# v1_1.net
KiCad netlist of a schematic drawn in EAGLE
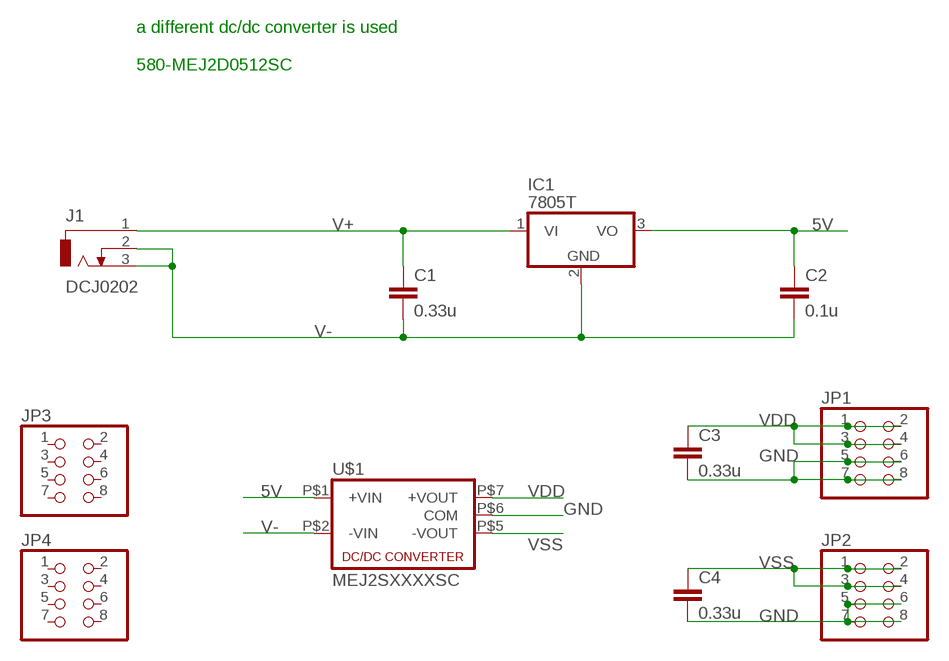
[diagram p0: schematic, sheet 1]

(export (version "E")
  (design (tool "Eeschema 10.0.6"))
  (components
    (comp (ref "C1")
      (value "0.33u")
      (footprint "eagle-import:C050-045X075")
      (libsource (lib "eagle-import") (part "C-EU050-045X075"))
    )
    (comp (ref "C2")
      (value "0.1u")
      (footprint "eagle-import:C050-045X075")
      (libsource (lib "eagle-import") (part "C-EU050-045X075"))
    )
    (comp (ref "C3")
      (value "0.33u")
      (footprint "eagle-import:C050-045X075")
      (libsource (lib "eagle-import") (part "C-EU050-045X075"))
    )
    (comp (ref "C4")
      (value "0.33u")
      (footprint "eagle-import:C050-045X075")
      (libsource (lib "eagle-import") (part "C-EU050-045X075"))
    )
    (comp (ref "IC1")
      (value "7805T")
      (footprint "eagle-import:TO220H")
      (libsource (lib "eagle-import") (part "78T05"))
    )
    (comp (ref "J1")
      (value "DCJ0202")
      (footprint "eagle-import:DCJ0202")
      (libsource (lib "eagle-import") (part "DCJ0202"))
    )
    (comp (ref "JP1")
      (value "PINHD-2X4")
      (footprint "eagle-import:2X04")
      (libsource (lib "eagle-import") (part "PINHD-2X4"))
    )
    (comp (ref "JP2")
      (value "PINHD-2X4")
      (footprint "eagle-import:2X04")
      (libsource (lib "eagle-import") (part "PINHD-2X4"))
    )
    (comp (ref "JP3")
      (value "PINHD-2X4")
      (footprint "eagle-import:2X04")
      (libsource (lib "eagle-import") (part "PINHD-2X4"))
    )
    (comp (ref "JP4")
      (value "PINHD-2X4")
      (footprint "eagle-import:2X04")
      (libsource (lib "eagle-import") (part "PINHD-2X4"))
    )
    (comp (ref "U$1")
      (value "MEJ2SXXXXSC")
      (footprint "eagle-import:NMA")
      (libsource (lib "eagle-import") (part "MEJ2SXXXXSC"))
    )
  )
  (nets
    (net (code "1") (name "/5V") (class "Default")
      (node (ref "C2") (pin "1") (pinfunction "1_1") (pintype "passive"))
      (node (ref "IC1") (pin "3") (pinfunction "VO_3") (pintype "passive"))
      (node (ref "U$1") (pin "P$1") (pinfunction "+VIN_P$1") (pintype "passive"))
    )
    (net (code "2") (name "/GND") (class "Default")
      (node (ref "C3") (pin "2") (pinfunction "2_2") (pintype "passive"))
      (node (ref "C4") (pin "2") (pinfunction "2_2") (pintype "passive"))
      (node (ref "JP1") (pin "5") (pinfunction "5_5") (pintype "passive"))
      (node (ref "JP1") (pin "6") (pinfunction "6_6") (pintype "passive"))
      (node (ref "JP1") (pin "7") (pinfunction "7_7") (pintype "passive"))
      (node (ref "JP1") (pin "8") (pinfunction "8_8") (pintype "passive"))
      (node (ref "JP2") (pin "5") (pinfunction "5_5") (pintype "passive"))
      (node (ref "JP2") (pin "6") (pinfunction "6_6") (pintype "passive"))
      (node (ref "JP2") (pin "7") (pinfunction "7_7") (pintype "passive"))
      (node (ref "JP2") (pin "8") (pinfunction "8_8") (pintype "passive"))
      (node (ref "U$1") (pin "P$6") (pinfunction "COM_P$6") (pintype "passive"))
    )
    (net (code "3") (name "/V+") (class "Default")
      (node (ref "C1") (pin "1") (pinfunction "1_1") (pintype "passive"))
      (node (ref "IC1") (pin "1") (pinfunction "VI_1") (pintype "input"))
      (node (ref "J1") (pin "1") (pinfunction "1_1") (pintype "passive"))
    )
    (net (code "4") (name "/V-") (class "Default")
      (node (ref "C1") (pin "2") (pinfunction "2_2") (pintype "passive"))
      (node (ref "C2") (pin "2") (pinfunction "2_2") (pintype "passive"))
      (node (ref "IC1") (pin "2") (pinfunction "GND_2") (pintype "passive"))
      (node (ref "J1") (pin "2") (pinfunction "2_2") (pintype "passive"))
      (node (ref "J1") (pin "3") (pinfunction "3_3") (pintype "passive"))
      (node (ref "U$1") (pin "P$2") (pinfunction "-VIN_P$2") (pintype "passive"))
    )
    (net (code "5") (name "/VDD") (class "Default")
      (node (ref "C3") (pin "1") (pinfunction "1_1") (pintype "passive"))
      (node (ref "JP1") (pin "1") (pinfunction "1_1") (pintype "passive"))
      (node (ref "JP1") (pin "2") (pinfunction "2_2") (pintype "passive"))
      (node (ref "JP1") (pin "3") (pinfunction "3_3") (pintype "passive"))
      (node (ref "JP1") (pin "4") (pinfunction "4_4") (pintype "passive"))
      (node (ref "U$1") (pin "P$7") (pinfunction "+VOUT_P$7") (pintype "passive"))
    )
    (net (code "6") (name "/VSS") (class "Default")
      (node (ref "C4") (pin "1") (pinfunction "1_1") (pintype "passive"))
      (node (ref "JP2") (pin "1") (pinfunction "1_1") (pintype "passive"))
      (node (ref "JP2") (pin "2") (pinfunction "2_2") (pintype "passive"))
      (node (ref "JP2") (pin "3") (pinfunction "3_3") (pintype "passive"))
      (node (ref "JP2") (pin "4") (pinfunction "4_4") (pintype "passive"))
      (node (ref "U$1") (pin "P$5") (pinfunction "-VOUT_P$5") (pintype "passive"))
    )
    (net (code "7") (name "unconnected-(JP3-Pad1)") (class "Default")
      (node (ref "JP3") (pin "1") (pinfunction "1_1") (pintype "passive"))
    )
    (net (code "8") (name "unconnected-(JP3-Pad2)") (class "Default")
      (node (ref "JP3") (pin "2") (pinfunction "2_2") (pintype "passive"))
    )
    (net (code "9") (name "unconnected-(JP3-Pad3)") (class "Default")
      (node (ref "JP3") (pin "3") (pinfunction "3_3") (pintype "passive"))
    )
    (net (code "10") (name "unconnected-(JP3-Pad4)") (class "Default")
      (node (ref "JP3") (pin "4") (pinfunction "4_4") (pintype "passive"))
    )
    (net (code "11") (name "unconnected-(JP3-Pad5)") (class "Default")
      (node (ref "JP3") (pin "5") (pinfunction "5_5") (pintype "passive"))
    )
    (net (code "12") (name "unconnected-(JP3-Pad6)") (class "Default")
      (node (ref "JP3") (pin "6") (pinfunction "6_6") (pintype "passive"))
    )
    (net (code "13") (name "unconnected-(JP3-Pad7)") (class "Default")
      (node (ref "JP3") (pin "7") (pinfunction "7_7") (pintype "passive"))
    )
    (net (code "14") (name "unconnected-(JP3-Pad8)") (class "Default")
      (node (ref "JP3") (pin "8") (pinfunction "8_8") (pintype "passive"))
    )
    (net (code "15") (name "unconnected-(JP4-Pad1)") (class "Default")
      (node (ref "JP4") (pin "1") (pinfunction "1_1") (pintype "passive"))
    )
    (net (code "16") (name "unconnected-(JP4-Pad2)") (class "Default")
      (node (ref "JP4") (pin "2") (pinfunction "2_2") (pintype "passive"))
    )
    (net (code "17") (name "unconnected-(JP4-Pad3)") (class "Default")
      (node (ref "JP4") (pin "3") (pinfunction "3_3") (pintype "passive"))
    )
    (net (code "18") (name "unconnected-(JP4-Pad4)") (class "Default")
      (node (ref "JP4") (pin "4") (pinfunction "4_4") (pintype "passive"))
    )
    (net (code "19") (name "unconnected-(JP4-Pad5)") (class "Default")
      (node (ref "JP4") (pin "5") (pinfunction "5_5") (pintype "passive"))
    )
    (net (code "20") (name "unconnected-(JP4-Pad6)") (class "Default")
      (node (ref "JP4") (pin "6") (pinfunction "6_6") (pintype "passive"))
    )
    (net (code "21") (name "unconnected-(JP4-Pad7)") (class "Default")
      (node (ref "JP4") (pin "7") (pinfunction "7_7") (pintype "passive"))
    )
    (net (code "22") (name "unconnected-(JP4-Pad8)") (class "Default")
      (node (ref "JP4") (pin "8") (pinfunction "8_8") (pintype "passive"))
    )
  )
)
